# com_port.net
KiCad netlist of a schematic drawn in Altium Designer
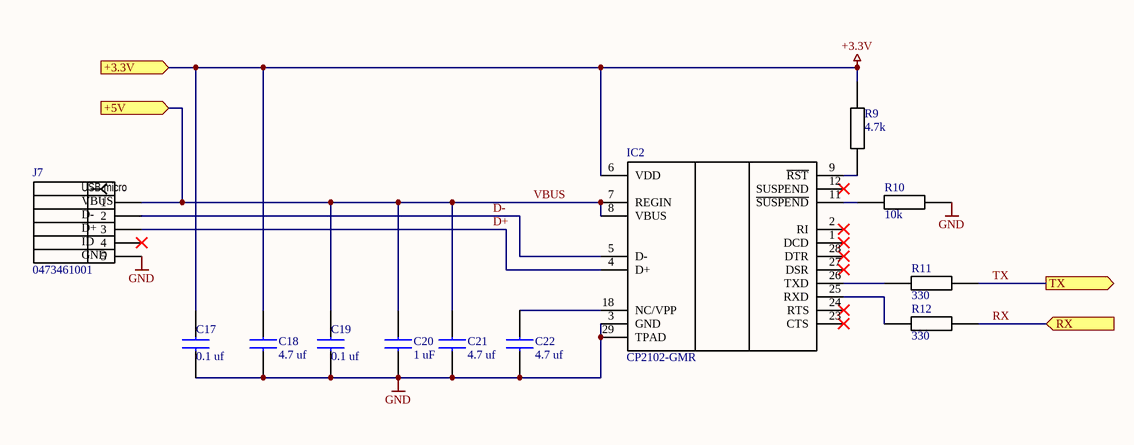
[diagram p0: com_port.SchDoc]

(export (version "E")
  (design (tool "Eeschema 10.0.6"))
  (components
    (comp (ref "C17")
      (value "0.1 uf")
      (footprint "SamacSys:CAPC1608X90N")
      (description "AVX 0.1 uF 16v dc 0603")
      (libsource (lib "RobotLib") (part "0603"))
    )
    (comp (ref "C18")
      (value "4.7 uf")
      (footprint "SamacSys:CAPC1608X90N")
      (description "AVX, SMD MLCC 4.7 uF 10 V dc, 0603")
      (libsource (lib "RobotLib") (part "0603"))
    )
    (comp (ref "C19")
      (value "0.1 uf")
      (footprint "SamacSys:CAPC1608X90N")
      (description "AVX 0.1 uF 16v dc 0603")
      (libsource (lib "RobotLib") (part "0603"))
    )
    (comp (ref "C20")
      (value "1 uF")
      (footprint "SamacSys:CAPC1608X90N")
      (description "AVX SMD 1uF 16V 0603")
      (libsource (lib "RobotLib") (part "0603"))
    )
    (comp (ref "C21")
      (value "4.7 uf")
      (footprint "SamacSys:CAPC1608X90N")
      (description "AVX, SMD MLCC 4.7 uF 10 V dc, 0603")
      (libsource (lib "RobotLib") (part "0603"))
    )
    (comp (ref "C22")
      (value "4.7 uf")
      (footprint "SamacSys:CAPC1608X90N")
      (description "AVX, SMD MLCC 4.7 uF 10 V dc, 0603")
      (libsource (lib "RobotLib") (part "0603"))
    )
    (comp (ref "IC2")
      (value "CP2102-GMR")
      (footprint "QFN50P500X500X100-29N-D")
      (description "Integrated Circuit")
      (fields (field (name "MOUSER PART NUMBER") "634-CP2102-GMR"))
      (libsource (lib "RobotLib") (part "CP2102-GMR"))
    )
    (comp (ref "J7")
      (value "0473461001")
      (footprint "SamacSys:0473461001")
      (description "Connector")
      (libsource (lib "RobotLib") (part "0473461001"))
    )
    (comp (ref "R9")
      (value "4.7k")
      (footprint "SamacSys:RESC1608X55N")
      (description "4.7k 0603")
      (fields
        (field (name "MANUFACTURER_PART_NUMBER") "CPF0603B100RE1")
        (field (name "MOUSER PART NUMBER") "279-CPF0603B100RE1")
      )
      (libsource (lib "RobotLib") (part "res 0603"))
    )
    (comp (ref "R10")
      (value "10k")
      (footprint "SamacSys:RESC1608X55N")
      (description "10k 0603")
      (fields
        (field (name "MANUFACTURER_PART_NUMBER") "CPF0603B100RE1")
        (field (name "MOUSER PART NUMBER") "279-CPF0603B100RE1")
      )
      (libsource (lib "") (part "res 0603_1"))
    )
    (comp (ref "R11")
      (value "330")
      (footprint "SamacSys:RESC1608X55N")
      (description "330 0603")
      (fields
        (field (name "MANUFACTURER_PART_NUMBER") "CPF0603B100RE1")
        (field (name "MOUSER PART NUMBER") "279-CPF0603B100RE1")
      )
      (libsource (lib "") (part "res 0603_1"))
    )
    (comp (ref "R12")
      (value "330")
      (footprint "SamacSys:RESC1608X55N")
      (description "330 0603")
      (fields
        (field (name "MANUFACTURER_PART_NUMBER") "CPF0603B100RE1")
        (field (name "MOUSER PART NUMBER") "279-CPF0603B100RE1")
      )
      (libsource (lib "") (part "res 0603_1"))
    )
  )
  (nets
    (net (code "1") (name "+3.3V") (class "Default")
      (node (ref "C17") (pin "2") (pinfunction "2_2") (pintype "passive"))
      (node (ref "C18") (pin "2") (pinfunction "2_2") (pintype "passive"))
      (node (ref "IC2") (pin "6") (pinfunction "VDD_6") (pintype "passive"))
      (node (ref "R9") (pin "2") (pinfunction "2_2") (pintype "passive"))
    )
    (net (code "2") (name "/D+") (class "Default")
      (node (ref "IC2") (pin "4") (pinfunction "D+_4") (pintype "passive"))
      (node (ref "J7") (pin "3") (pinfunction "3_3") (pintype "passive"))
    )
    (net (code "3") (name "/D-") (class "Default")
      (node (ref "IC2") (pin "5") (pinfunction "D-_5") (pintype "passive"))
      (node (ref "J7") (pin "2") (pinfunction "2_2") (pintype "passive"))
    )
    (net (code "4") (name "/RX") (class "Default")
      (node (ref "R12") (pin "1") (pinfunction "1_1") (pintype "passive"))
    )
    (net (code "5") (name "/TX") (class "Default")
      (node (ref "R11") (pin "1") (pinfunction "1_1") (pintype "passive"))
    )
    (net (code "6") (name "/VBUS") (class "Default")
      (node (ref "C19") (pin "2") (pinfunction "2_2") (pintype "passive"))
      (node (ref "C20") (pin "2") (pinfunction "2_2") (pintype "passive"))
      (node (ref "C21") (pin "2") (pinfunction "2_2") (pintype "passive"))
      (node (ref "IC2") (pin "7") (pinfunction "REGIN_7") (pintype "passive"))
      (node (ref "IC2") (pin "8") (pinfunction "VBUS_8") (pintype "passive"))
      (node (ref "J7") (pin "1") (pinfunction "1_1") (pintype "passive"))
    )
    (net (code "7") (name "GND") (class "Default")
      (node (ref "C17") (pin "1") (pinfunction "1_1") (pintype "passive"))
      (node (ref "C18") (pin "1") (pinfunction "1_1") (pintype "passive"))
      (node (ref "C19") (pin "1") (pinfunction "1_1") (pintype "passive"))
      (node (ref "C20") (pin "1") (pinfunction "1_1") (pintype "passive"))
      (node (ref "C21") (pin "1") (pinfunction "1_1") (pintype "passive"))
      (node (ref "C22") (pin "1") (pinfunction "1_1") (pintype "passive"))
      (node (ref "IC2") (pin "29") (pinfunction "TPAD_29") (pintype "passive"))
      (node (ref "IC2") (pin "3") (pinfunction "GND_3") (pintype "passive"))
      (node (ref "J7") (pin "5") (pinfunction "5_5") (pintype "passive"))
      (node (ref "R10") (pin "1") (pinfunction "1_1") (pintype "passive"))
    )
    (net (code "8") (name "Net-(IC2-NC{slash}VPP)") (class "Default")
      (node (ref "C22") (pin "2") (pinfunction "2_2") (pintype "passive"))
      (node (ref "IC2") (pin "18") (pinfunction "NC/VPP_18") (pintype "passive"))
    )
    (net (code "9") (name "Net-(IC2-RXD)") (class "Default")
      (node (ref "IC2") (pin "25") (pinfunction "RXD_25") (pintype "passive"))
      (node (ref "R12") (pin "2") (pinfunction "2_2") (pintype "passive"))
    )
    (net (code "10") (name "Net-(IC2-TXD)") (class "Default")
      (node (ref "IC2") (pin "26") (pinfunction "TXD_26") (pintype "passive"))
      (node (ref "R11") (pin "2") (pinfunction "2_2") (pintype "passive"))
    )
    (net (code "11") (name "Net-(IC2-~{RST})") (class "Default")
      (node (ref "IC2") (pin "9") (pinfunction "~{RST}_9") (pintype "passive"))
      (node (ref "R9") (pin "1") (pinfunction "1_1") (pintype "passive"))
    )
    (net (code "12") (name "Net-(IC2-~{SUSPEND})") (class "Default")
      (node (ref "IC2") (pin "11") (pinfunction "~{SUSPEND}_11") (pintype "passive"))
      (node (ref "R10") (pin "2") (pinfunction "2_2") (pintype "passive"))
    )
    (net (code "13") (name "unconnected-(IC2-CTS-Pad23)") (class "Default")
      (node (ref "IC2") (pin "23") (pinfunction "CTS_23") (pintype "passive+no_connect"))
    )
    (net (code "14") (name "unconnected-(IC2-DCD-Pad1)") (class "Default")
      (node (ref "IC2") (pin "1") (pinfunction "DCD_1") (pintype "passive+no_connect"))
    )
    (net (code "15") (name "unconnected-(IC2-DSR-Pad27)") (class "Default")
      (node (ref "IC2") (pin "27") (pinfunction "DSR_27") (pintype "passive+no_connect"))
    )
    (net (code "16") (name "unconnected-(IC2-DTR-Pad28)") (class "Default")
      (node (ref "IC2") (pin "28") (pinfunction "DTR_28") (pintype "passive+no_connect"))
    )
    (net (code "17") (name "unconnected-(IC2-RI-Pad2)") (class "Default")
      (node (ref "IC2") (pin "2") (pinfunction "RI_2") (pintype "passive+no_connect"))
    )
    (net (code "18") (name "unconnected-(IC2-RTS-Pad24)") (class "Default")
      (node (ref "IC2") (pin "24") (pinfunction "RTS_24") (pintype "passive+no_connect"))
    )
    (net (code "19") (name "unconnected-(IC2-SUSPEND-Pad12)") (class "Default")
      (node (ref "IC2") (pin "12") (pinfunction "SUSPEND_12") (pintype "passive+no_connect"))
    )
    (net (code "20") (name "unconnected-(J7-Pad4)") (class "Default")
      (node (ref "J7") (pin "4") (pinfunction "4_4") (pintype "passive+no_connect"))
    )
  )
)
